# MCU_ATmega4809.net
KiCad netlist of a schematic drawn in Altium Designer
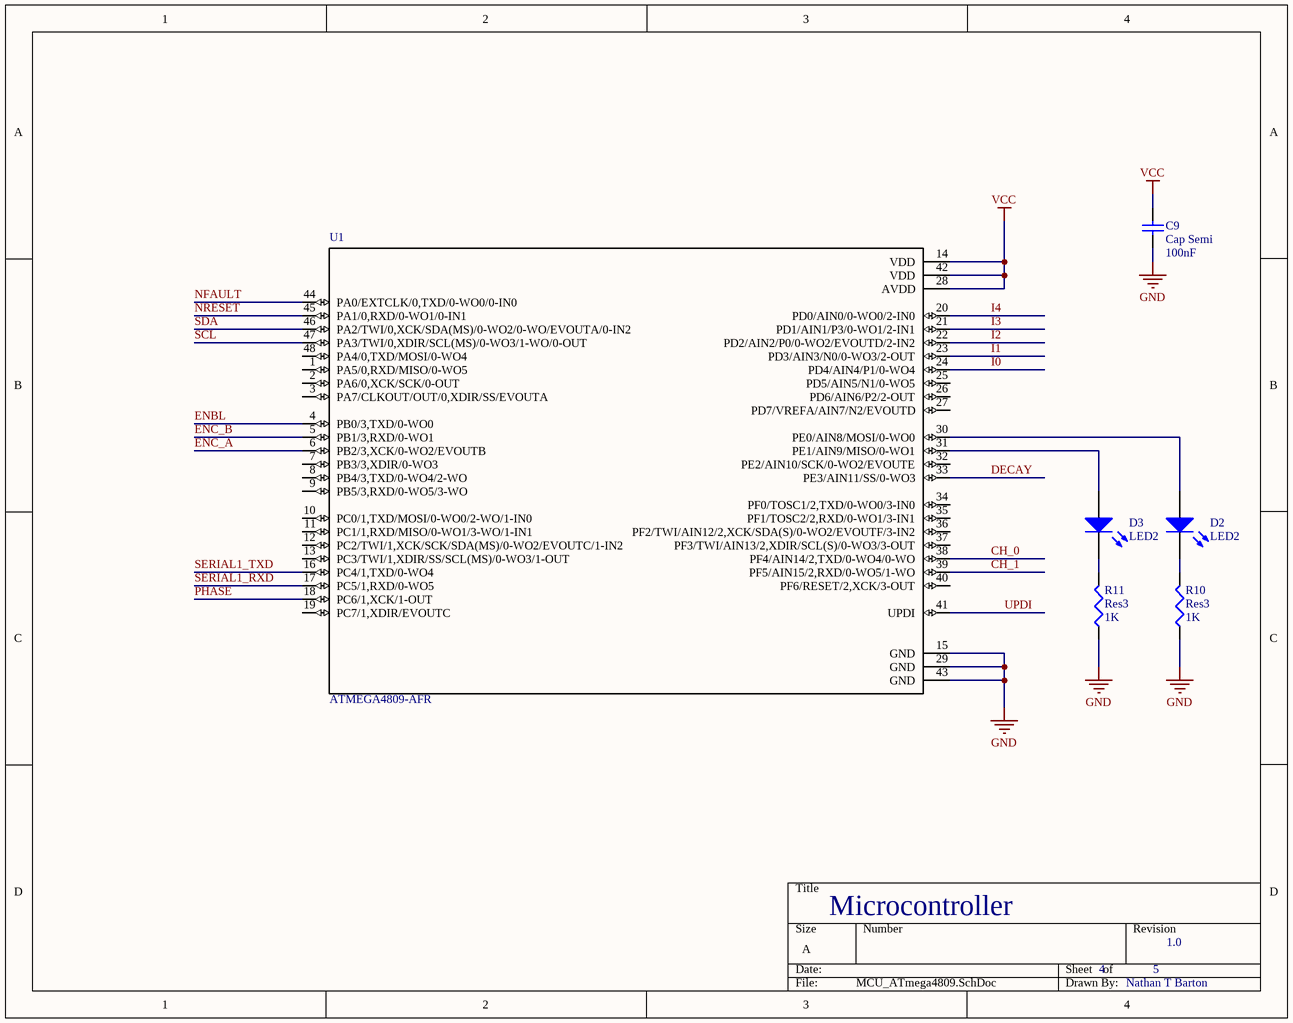
[diagram p0: MCU_ATmega4809.SchDoc]

(export (version "E")
  (design (tool "Eeschema 10.0.6"))
  (components
    (comp (ref "C9")
      (value "Cap Semi")
      (footprint "C1206")
      (description "Capacitor (Semiconductor SIM Model)")
      (fields (field (name "ALTIUM_VALUE") "100nF") (field (name "PUBLISHER") "Altium Limited"))
      (libsource (lib "Miscellaneous Devices") (part "Cap Semi"))
    )
    (comp (ref "D2")
      (value "LED2")
      (footprint "3.2X1.6X1.1")
      (description "Typical RED, GREEN, YELLOW, AMBER GaAs LED")
      (fields (field (name "PUBLISHER") "Altium Limited"))
      (libsource (lib "Miscellaneous Devices") (part "LED2"))
    )
    (comp (ref "D3")
      (value "LED2")
      (footprint "3.2X1.6X1.1")
      (description "Typical RED, GREEN, YELLOW, AMBER GaAs LED")
      (fields (field (name "PUBLISHER") "Altium Limited"))
      (libsource (lib "Miscellaneous Devices") (part "LED2"))
    )
    (comp (ref "R10")
      (value "Res3")
      (footprint "J1-0603")
      (description "Resistor")
      (fields (field (name "ALTIUM_VALUE") "1K") (field (name "PUBLISHER") "Altium Limited"))
      (libsource (lib "Miscellaneous Devices") (part "Res3"))
    )
    (comp (ref "R11")
      (value "Res3")
      (footprint "J1-0603")
      (description "Resistor")
      (fields (field (name "ALTIUM_VALUE") "1K") (field (name "PUBLISHER") "Altium Limited"))
      (libsource (lib "Miscellaneous Devices") (part "Res3"))
    )
    (comp (ref "U1")
      (value "ATMEGA4809-AFR")
      (footprint "*QFP50P900X900X120-48N")
      (description "20MHz 48KB TQFP48 Ind 125C Green T&R")
      (fields (field (name "MF") "Microchip"))
      (libsource (lib "spoolbot_library") (part "ATMEGA4809-AFR"))
    )
  )
  (nets
    (net (code "1") (name "/CH_0") (class "Default")
      (node (ref "U1") (pin "38") (pinfunction "PF4/AIN14/2,TXD/0-WO4/0-WO_38") (pintype "bidirectional"))
    )
    (net (code "2") (name "/CH_1") (class "Default")
      (node (ref "U1") (pin "39") (pinfunction "PF5/AIN15/2,RXD/0-WO5/1-WO_39") (pintype "bidirectional"))
    )
    (net (code "3") (name "/DECAY") (class "Default")
      (node (ref "U1") (pin "33") (pinfunction "PE3/AIN11/SS/0-WO3_33") (pintype "bidirectional"))
    )
    (net (code "4") (name "/ENBL") (class "Default")
      (node (ref "U1") (pin "4") (pinfunction "PB0/3,TXD/0-WO0_4") (pintype "bidirectional"))
    )
    (net (code "5") (name "/ENC_A") (class "Default")
      (node (ref "U1") (pin "6") (pinfunction "PB2/3,XCK/0-WO2/EVOUTB_6") (pintype "bidirectional"))
    )
    (net (code "6") (name "/ENC_B") (class "Default")
      (node (ref "U1") (pin "5") (pinfunction "PB1/3,RXD/0-WO1_5") (pintype "bidirectional"))
    )
    (net (code "7") (name "/I0") (class "Default")
      (node (ref "U1") (pin "24") (pinfunction "PD4/AIN4/P1/0-WO4_24") (pintype "bidirectional"))
    )
    (net (code "8") (name "/I1") (class "Default")
      (node (ref "U1") (pin "23") (pinfunction "PD3/AIN3/N0/0-WO3/2-OUT_23") (pintype "bidirectional"))
    )
    (net (code "9") (name "/I2") (class "Default")
      (node (ref "U1") (pin "22") (pinfunction "PD2/AIN2/P0/0-WO2/EVOUTD/2-IN2_22") (pintype "bidirectional"))
    )
    (net (code "10") (name "/I3") (class "Default")
      (node (ref "U1") (pin "21") (pinfunction "PD1/AIN1/P3/0-WO1/2-IN1_21") (pintype "bidirectional"))
    )
    (net (code "11") (name "/I4") (class "Default")
      (node (ref "U1") (pin "20") (pinfunction "PD0/AIN0/0-WO0/2-IN0_20") (pintype "bidirectional"))
    )
    (net (code "12") (name "/NFAULT") (class "Default")
      (node (ref "U1") (pin "44") (pinfunction "PA0/EXTCLK/0,TXD/0-WO0/0-IN0_44") (pintype "bidirectional"))
    )
    (net (code "13") (name "/NRESET") (class "Default")
      (node (ref "U1") (pin "45") (pinfunction "PA1/0,RXD/0-WO1/0-IN1_45") (pintype "bidirectional"))
    )
    (net (code "14") (name "/PHASE") (class "Default")
      (node (ref "U1") (pin "18") (pinfunction "PC6/1,XCK/1-OUT_18") (pintype "bidirectional"))
    )
    (net (code "15") (name "/SCL") (class "Default")
      (node (ref "U1") (pin "47") (pinfunction "PA3/TWI/0,XDIR/SCL(MS)/0-WO3/1-WO/0-OUT_47") (pintype "bidirectional"))
    )
    (net (code "16") (name "/SDA") (class "Default")
      (node (ref "U1") (pin "46") (pinfunction "PA2/TWI/0,XCK/SDA(MS)/0-WO2/0-WO/EVOUTA/0-IN2_46") (pintype "bidirectional"))
    )
    (net (code "17") (name "/SERIAL1_RXD") (class "Default")
      (node (ref "U1") (pin "17") (pinfunction "PC5/1,RXD/0-WO5_17") (pintype "bidirectional"))
    )
    (net (code "18") (name "/SERIAL1_TXD") (class "Default")
      (node (ref "U1") (pin "16") (pinfunction "PC4/1,TXD/0-WO4_16") (pintype "bidirectional"))
    )
    (net (code "19") (name "/UPDI") (class "Default")
      (node (ref "U1") (pin "41") (pinfunction "UPDI_41") (pintype "bidirectional"))
    )
    (net (code "20") (name "GND") (class "Default")
      (node (ref "C9") (pin "1") (pinfunction "1_1") (pintype "passive"))
      (node (ref "R10") (pin "1") (pinfunction "1_1") (pintype "passive"))
      (node (ref "R11") (pin "1") (pinfunction "1_1") (pintype "passive"))
      (node (ref "U1") (pin "15") (pinfunction "GND_15") (pintype "power_in"))
      (node (ref "U1") (pin "29") (pinfunction "GND_29") (pintype "power_in"))
      (node (ref "U1") (pin "43") (pinfunction "GND_43") (pintype "power_in"))
    )
    (net (code "21") (name "Net-(D2-A)") (class "Default")
      (node (ref "D2") (pin "1") (pinfunction "A_1") (pintype "passive"))
      (node (ref "U1") (pin "30") (pinfunction "PE0/AIN8/MOSI/0-WO0_30") (pintype "bidirectional"))
    )
    (net (code "22") (name "Net-(D2-K)") (class "Default")
      (node (ref "D2") (pin "2") (pinfunction "K_2") (pintype "passive"))
      (node (ref "R10") (pin "2") (pinfunction "2_2") (pintype "passive"))
    )
    (net (code "23") (name "Net-(D3-A)") (class "Default")
      (node (ref "D3") (pin "1") (pinfunction "A_1") (pintype "passive"))
      (node (ref "U1") (pin "31") (pinfunction "PE1/AIN9/MISO/0-WO1_31") (pintype "bidirectional"))
    )
    (net (code "24") (name "Net-(D3-K)") (class "Default")
      (node (ref "D3") (pin "2") (pinfunction "K_2") (pintype "passive"))
      (node (ref "R11") (pin "2") (pinfunction "2_2") (pintype "passive"))
    )
    (net (code "25") (name "VCC") (class "Default")
      (node (ref "C9") (pin "2") (pinfunction "2_2") (pintype "passive"))
      (node (ref "U1") (pin "14") (pinfunction "VDD_14") (pintype "power_in"))
      (node (ref "U1") (pin "28") (pinfunction "AVDD_28") (pintype "power_in"))
      (node (ref "U1") (pin "42") (pinfunction "VDD_42") (pintype "power_in"))
    )
    (net (code "26") (name "unconnected-(U1-PA4{slash}0,TXD{slash}MOSI{slash}0-WO4-Pad48)") (class "Default")
      (node (ref "U1") (pin "48") (pinfunction "PA4/0,TXD/MOSI/0-WO4_48") (pintype "bidirectional"))
    )
    (net (code "27") (name "unconnected-(U1-PA5{slash}0,RXD{slash}MISO{slash}0-WO5-Pad1)") (class "Default")
      (node (ref "U1") (pin "1") (pinfunction "PA5/0,RXD/MISO/0-WO5_1") (pintype "bidirectional"))
    )
    (net (code "28") (name "unconnected-(U1-PA6{slash}0,XCK{slash}SCK{slash}0-OUT-Pad2)") (class "Default")
      (node (ref "U1") (pin "2") (pinfunction "PA6/0,XCK/SCK/0-OUT_2") (pintype "bidirectional"))
    )
    (net (code "29") (name "unconnected-(U1-PA7{slash}CLKOUT{slash}OUT{slash}0,XDIR{slash}SS{slash}EVOUTA-Pad3)") (class "Default")
      (node (ref "U1") (pin "3") (pinfunction "PA7/CLKOUT/OUT/0,XDIR/SS/EVOUTA_3") (pintype "bidirectional"))
    )
    (net (code "30") (name "unconnected-(U1-PB3{slash}3,XDIR{slash}0-WO3-Pad7)") (class "Default")
      (node (ref "U1") (pin "7") (pinfunction "PB3/3,XDIR/0-WO3_7") (pintype "bidirectional"))
    )
    (net (code "31") (name "unconnected-(U1-PB4{slash}3,TXD{slash}0-WO4{slash}2-WO-Pad8)") (class "Default")
      (node (ref "U1") (pin "8") (pinfunction "PB4/3,TXD/0-WO4/2-WO_8") (pintype "bidirectional"))
    )
    (net (code "32") (name "unconnected-(U1-PB5{slash}3,RXD{slash}0-WO5{slash}3-WO-Pad9)") (class "Default")
      (node (ref "U1") (pin "9") (pinfunction "PB5/3,RXD/0-WO5/3-WO_9") (pintype "bidirectional"))
    )
    (net (code "33") (name "unconnected-(U1-PC0{slash}1,TXD{slash}MOSI{slash}0-WO0{slash}2-WO{slash}1-IN0-Pad10)") (class "Default")
      (node (ref "U1") (pin "10") (pinfunction "PC0/1,TXD/MOSI/0-WO0/2-WO/1-IN0_10") (pintype "bidirectional"))
    )
    (net (code "34") (name "unconnected-(U1-PC1{slash}1,RXD{slash}MISO{slash}0-WO1{slash}3-WO{slash}1-IN1-Pad11)") (class "Default")
      (node (ref "U1") (pin "11") (pinfunction "PC1/1,RXD/MISO/0-WO1/3-WO/1-IN1_11") (pintype "bidirectional"))
    )
    (net (code "35") (name "unconnected-(U1-PC2{slash}TWI{slash}1,XCK{slash}SCK{slash}SDA(MS){slash}0-WO2{slash}EVOUTC{slash}1-IN2-Pad12)") (class "Default")
      (node (ref "U1") (pin "12") (pinfunction "PC2/TWI/1,XCK/SCK/SDA(MS)/0-WO2/EVOUTC/1-IN2_12") (pintype "bidirectional"))
    )
    (net (code "36") (name "unconnected-(U1-PC3{slash}TWI{slash}1,XDIR{slash}SS{slash}SCL(MS){slash}0-WO3{slash}1-OUT-Pad13)") (class "Default")
      (node (ref "U1") (pin "13") (pinfunction "PC3/TWI/1,XDIR/SS/SCL(MS)/0-WO3/1-OUT_13") (pintype "bidirectional"))
    )
    (net (code "37") (name "unconnected-(U1-PC7{slash}1,XDIR{slash}EVOUTC-Pad19)") (class "Default")
      (node (ref "U1") (pin "19") (pinfunction "PC7/1,XDIR/EVOUTC_19") (pintype "bidirectional"))
    )
    (net (code "38") (name "unconnected-(U1-PD5{slash}AIN5{slash}N1{slash}0-WO5-Pad25)") (class "Default")
      (node (ref "U1") (pin "25") (pinfunction "PD5/AIN5/N1/0-WO5_25") (pintype "bidirectional"))
    )
    (net (code "39") (name "unconnected-(U1-PD6{slash}AIN6{slash}P2{slash}2-OUT-Pad26)") (class "Default")
      (node (ref "U1") (pin "26") (pinfunction "PD6/AIN6/P2/2-OUT_26") (pintype "bidirectional"))
    )
    (net (code "40") (name "unconnected-(U1-PD7{slash}VREFA{slash}AIN7{slash}N2{slash}EVOUTD-Pad27)") (class "Default")
      (node (ref "U1") (pin "27") (pinfunction "PD7/VREFA/AIN7/N2/EVOUTD_27") (pintype "bidirectional"))
    )
    (net (code "41") (name "unconnected-(U1-PE2{slash}AIN10{slash}SCK{slash}0-WO2{slash}EVOUTE-Pad32)") (class "Default")
      (node (ref "U1") (pin "32") (pinfunction "PE2/AIN10/SCK/0-WO2/EVOUTE_32") (pintype "bidirectional"))
    )
    (net (code "42") (name "unconnected-(U1-PF0{slash}TOSC1{slash}2,TXD{slash}0-WO0{slash}3-IN0-Pad34)") (class "Default")
      (node (ref "U1") (pin "34") (pinfunction "PF0/TOSC1/2,TXD/0-WO0/3-IN0_34") (pintype "bidirectional"))
    )
    (net (code "43") (name "unconnected-(U1-PF1{slash}TOSC2{slash}2,RXD{slash}0-WO1{slash}3-IN1-Pad35)") (class "Default")
      (node (ref "U1") (pin "35") (pinfunction "PF1/TOSC2/2,RXD/0-WO1/3-IN1_35") (pintype "bidirectional"))
    )
    (net (code "44") (name "unconnected-(U1-PF2{slash}TWI{slash}AIN12{slash}2,XCK{slash}SDA(S){slash}0-WO2{slash}EVOUTF{slash}3-IN2-Pad36)") (class "Default")
      (node (ref "U1") (pin "36") (pinfunction "PF2/TWI/AIN12/2,XCK/SDA(S)/0-WO2/EVOUTF/3-IN2_36") (pintype "bidirectional"))
    )
    (net (code "45") (name "unconnected-(U1-PF3{slash}TWI{slash}AIN13{slash}2,XDIR{slash}SCL(S){slash}0-WO3{slash}3-OUT-Pad37)") (class "Default")
      (node (ref "U1") (pin "37") (pinfunction "PF3/TWI/AIN13/2,XDIR/SCL(S)/0-WO3/3-OUT_37") (pintype "bidirectional"))
    )
    (net (code "46") (name "unconnected-(U1-PF6{slash}RESET{slash}2,XCK{slash}3-OUT-Pad40)") (class "Default")
      (node (ref "U1") (pin "40") (pinfunction "PF6/RESET/2,XCK/3-OUT_40") (pintype "bidirectional"))
    )
  )
)
